# SIX_OUTPORT-V2.net
KiCad netlist of a schematic drawn in Altium Designer
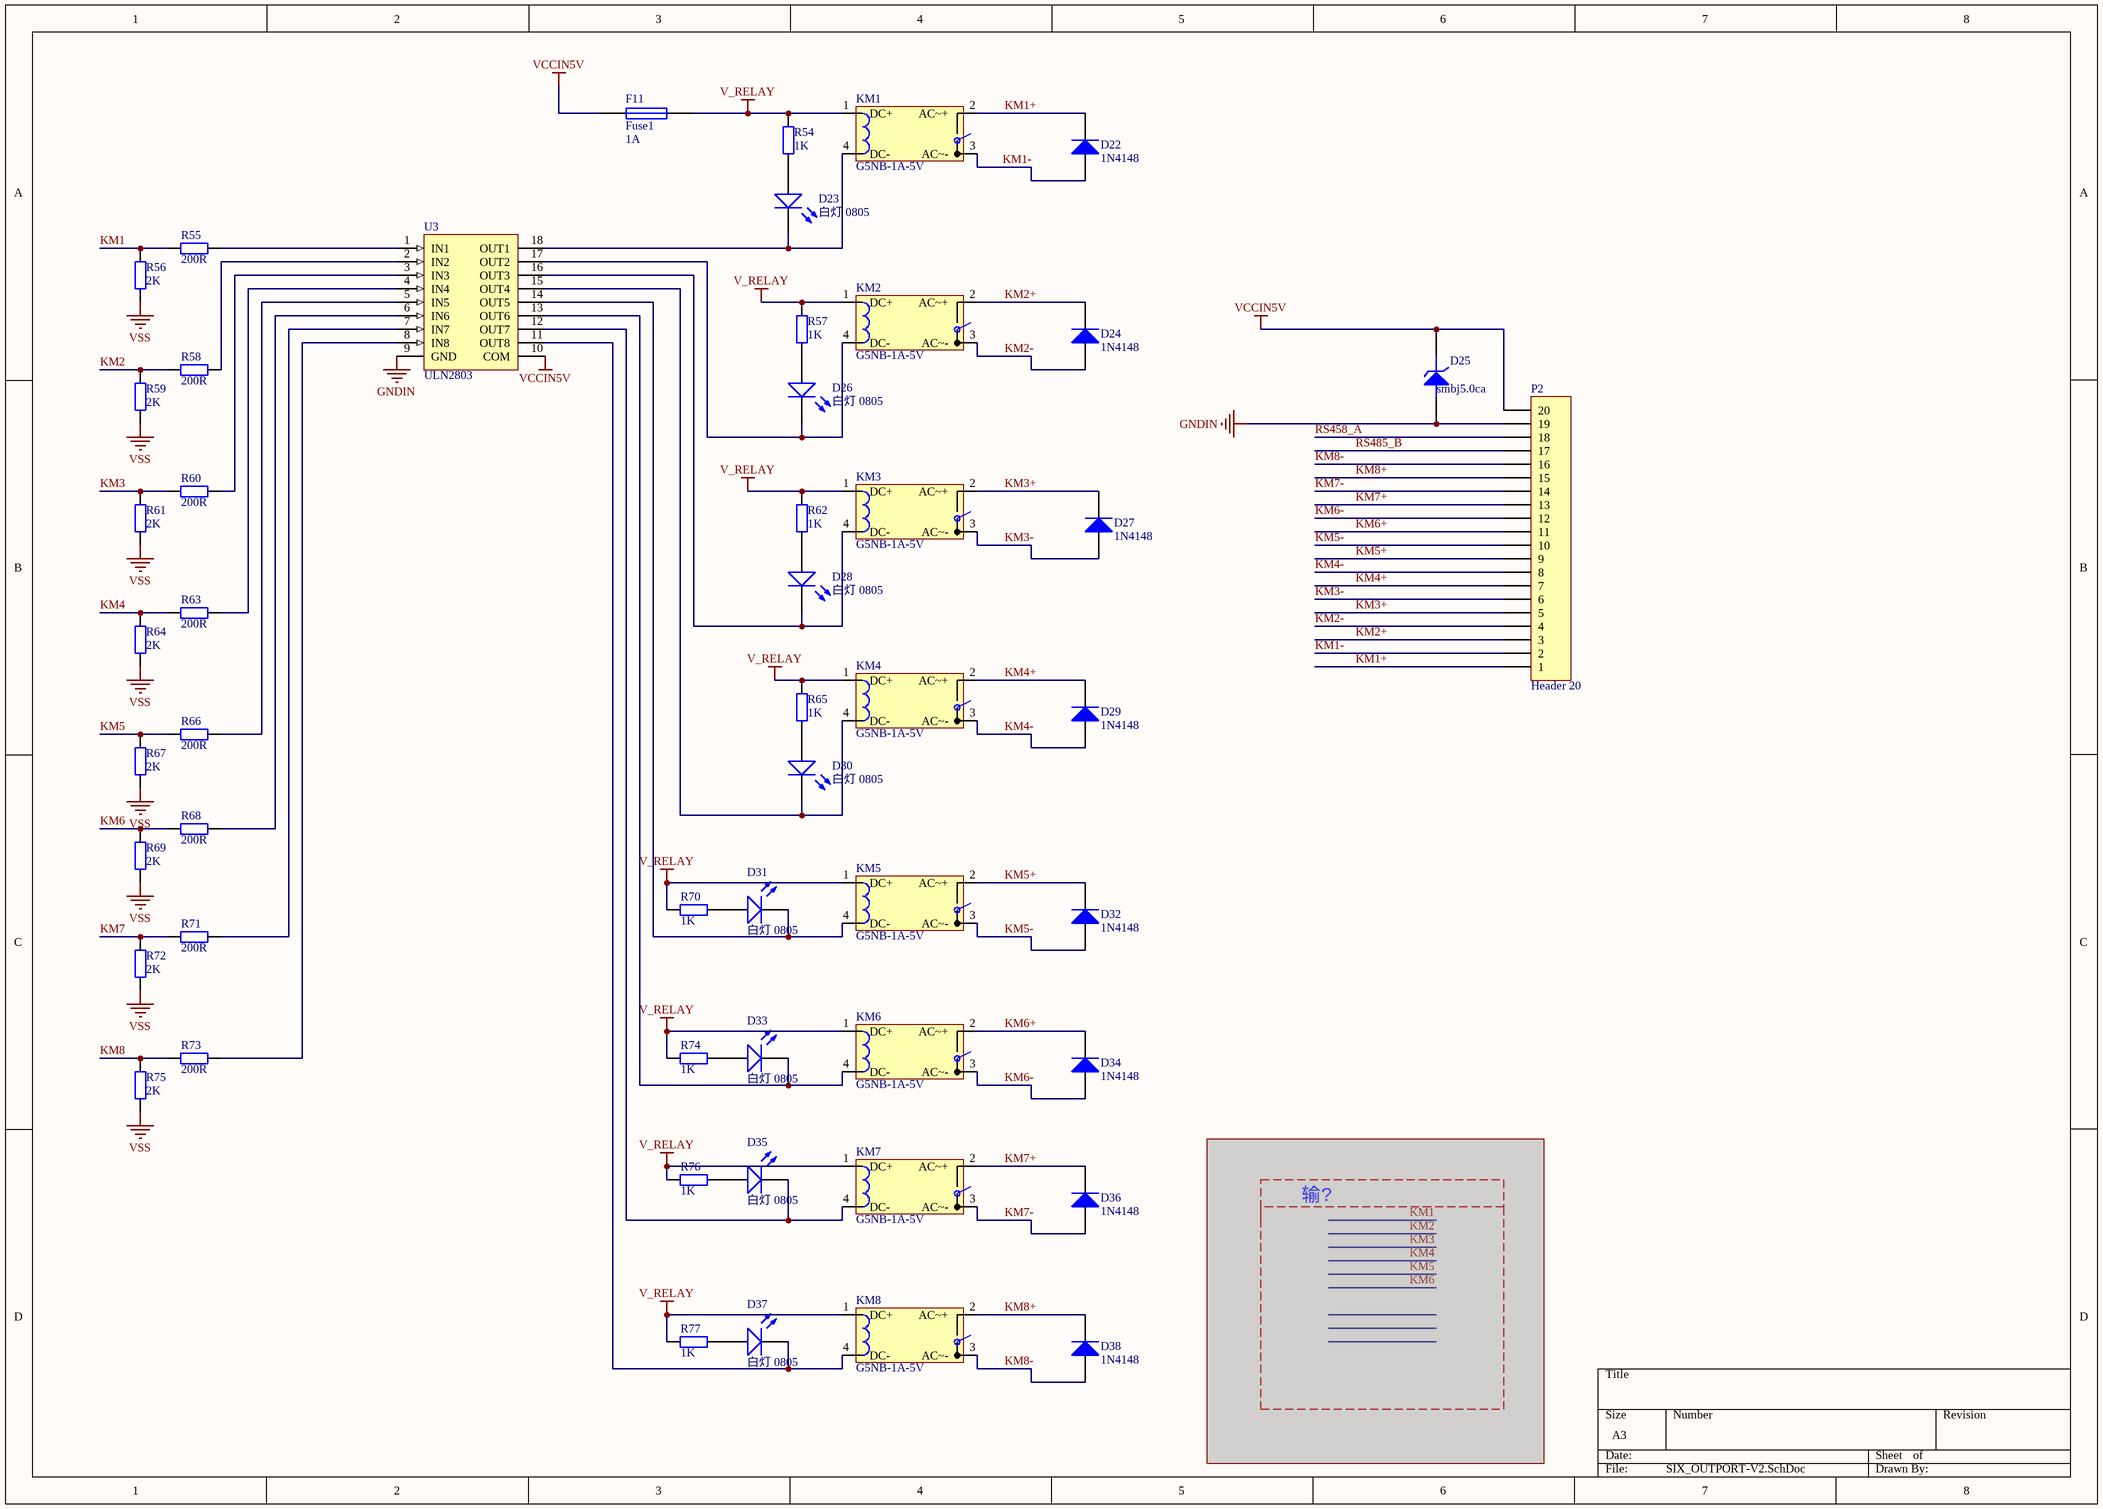
[diagram p0: SIX_OUTPORT-V2.SchDoc]

(export (version "E")
  (design (tool "Eeschema 10.0.6"))
  (components
    (comp (ref "D22")
      (value "1N4148")
      (footprint "LC-LL-34")
      (description "Default Diode")
      (fields (field (name "PUBLISHER") "Altium Limited"))
      (libsource (lib "Miscellaneous Devices") (part "Diode"))
    )
    (comp (ref "D23")
      (value "白灯 0805")
      (footprint "LC-0603_LED_S1")
      (description "发光二极管")
      (libsource (lib "Miscellaneous Devices LC") (part "0805 白灯"))
    )
    (comp (ref "D24")
      (value "1N4148")
      (footprint "LC-LL-34")
      (description "Default Diode")
      (fields (field (name "PUBLISHER") "Altium Limited"))
      (libsource (lib "Miscellaneous Devices") (part "Diode"))
    )
    (comp (ref "D25")
      (value "smbj5.0ca")
      (footprint "LC-SMB(DO-214AA)_S1")
      (description "Zener Diode")
      (libsource (lib "Miscellaneous Devices") (part "ZENER3"))
    )
    (comp (ref "D26")
      (value "白灯 0805")
      (footprint "LC-0603_LED_S1")
      (description "发光二极管")
      (libsource (lib "Miscellaneous Devices LC") (part "0805 白灯"))
    )
    (comp (ref "D27")
      (value "1N4148")
      (footprint "LC-LL-34")
      (description "Default Diode")
      (fields (field (name "PUBLISHER") "Altium Limited"))
      (libsource (lib "Miscellaneous Devices") (part "Diode"))
    )
    (comp (ref "D28")
      (value "白灯 0805")
      (footprint "LC-0603_LED_S1")
      (description "发光二极管")
      (libsource (lib "Miscellaneous Devices LC") (part "0805 白灯"))
    )
    (comp (ref "D29")
      (value "1N4148")
      (footprint "LC-LL-34")
      (description "Default Diode")
      (fields (field (name "PUBLISHER") "Altium Limited"))
      (libsource (lib "Miscellaneous Devices") (part "Diode"))
    )
    (comp (ref "D30")
      (value "白灯 0805")
      (footprint "LC-0603_LED_S1")
      (description "发光二极管")
      (libsource (lib "Miscellaneous Devices LC") (part "0805 白灯"))
    )
    (comp (ref "D31")
      (value "白灯 0805")
      (footprint "LC-0603_LED_S1")
      (description "发光二极管")
      (libsource (lib "Miscellaneous Devices LC") (part "0805 白灯"))
    )
    (comp (ref "D32")
      (value "1N4148")
      (footprint "LC-LL-34")
      (description "Default Diode")
      (fields (field (name "PUBLISHER") "Altium Limited"))
      (libsource (lib "Miscellaneous Devices") (part "Diode"))
    )
    (comp (ref "D33")
      (value "白灯 0805")
      (footprint "LC-0603_LED_S1")
      (description "发光二极管")
      (libsource (lib "Miscellaneous Devices LC") (part "0805 白灯"))
    )
    (comp (ref "D34")
      (value "1N4148")
      (footprint "LC-LL-34")
      (description "Default Diode")
      (fields (field (name "PUBLISHER") "Altium Limited"))
      (libsource (lib "Miscellaneous Devices") (part "Diode"))
    )
    (comp (ref "D35")
      (value "白灯 0805")
      (footprint "LC-0603_LED_S1")
      (description "发光二极管")
      (libsource (lib "Miscellaneous Devices LC") (part "0805 白灯"))
    )
    (comp (ref "D36")
      (value "1N4148")
      (footprint "LC-LL-34")
      (description "Default Diode")
      (fields (field (name "PUBLISHER") "Altium Limited"))
      (libsource (lib "Miscellaneous Devices") (part "Diode"))
    )
    (comp (ref "D37")
      (value "白灯 0805")
      (footprint "LC-0603_LED_S1")
      (description "发光二极管")
      (libsource (lib "Miscellaneous Devices LC") (part "0805 白灯"))
    )
    (comp (ref "D38")
      (value "1N4148")
      (footprint "LC-LL-34")
      (description "Default Diode")
      (fields (field (name "PUBLISHER") "Altium Limited"))
      (libsource (lib "Miscellaneous Devices") (part "Diode"))
    )
    (comp (ref "F11")
      (value "Fuse1")
      (footprint "LC-1206_R")
      (description "保险丝")
      (fields (field (name "ALTIUM_VALUE") "1A"))
      (libsource (lib "fszhang") (part "Fuse1"))
    )
    (comp (ref "KM1")
      (value "G5NB-1A-5V")
      (footprint "G5NB-1A-5V")
      (libsource (lib "fszhang") (part "G5NB-1A-5V"))
    )
    (comp (ref "KM2")
      (value "G5NB-1A-5V")
      (footprint "G5NB-1A-5V")
      (libsource (lib "fszhang") (part "G5NB-1A-5V"))
    )
    (comp (ref "KM3")
      (value "G5NB-1A-5V")
      (footprint "G5NB-1A-5V")
      (libsource (lib "fszhang") (part "G5NB-1A-5V"))
    )
    (comp (ref "KM4")
      (value "G5NB-1A-5V")
      (footprint "G5NB-1A-5V")
      (libsource (lib "fszhang") (part "G5NB-1A-5V"))
    )
    (comp (ref "KM5")
      (value "G5NB-1A-5V")
      (footprint "G5NB-1A-5V")
      (libsource (lib "fszhang") (part "G5NB-1A-5V"))
    )
    (comp (ref "KM6")
      (value "G5NB-1A-5V")
      (footprint "G5NB-1A-5V")
      (libsource (lib "fszhang") (part "G5NB-1A-5V"))
    )
    (comp (ref "KM7")
      (value "G5NB-1A-5V")
      (footprint "G5NB-1A-5V")
      (libsource (lib "fszhang") (part "G5NB-1A-5V"))
    )
    (comp (ref "KM8")
      (value "G5NB-1A-5V")
      (footprint "G5NB-1A-5V")
      (libsource (lib "fszhang") (part "G5NB-1A-5V"))
    )
    (comp (ref "P2")
      (value "Header 20")
      (footprint "HDR_5.0_20P")
      (description "Header, 20-Pin")
      (fields (field (name "PUBLISHER") "Altium Limited"))
      (libsource (lib "Miscellaneous Connectors") (part "Header 20"))
    )
    (comp (ref "R54")
      (value "1K")
      (footprint "LC-0603_R")
      (description "Resistor")
      (fields (field (name "PUBLISHER") "Altium Limited"))
      (libsource (lib "") (part "Res2_1"))
    )
    (comp (ref "R55")
      (value "200R")
      (footprint "LC-0603_R")
      (description "Resistor")
      (fields (field (name "PUBLISHER") "Altium Limited"))
      (libsource (lib "") (part "Res2_2"))
    )
    (comp (ref "R56")
      (value "2K")
      (footprint "LC-0603_R")
      (description "Resistor")
      (fields (field (name "PUBLISHER") "Altium Limited"))
      (libsource (lib "") (part "Res2_1"))
    )
    (comp (ref "R57")
      (value "1K")
      (footprint "LC-0603_R")
      (description "Resistor")
      (fields (field (name "PUBLISHER") "Altium Limited"))
      (libsource (lib "") (part "Res2_1"))
    )
    (comp (ref "R58")
      (value "200R")
      (footprint "LC-0603_R")
      (description "Resistor")
      (fields (field (name "PUBLISHER") "Altium Limited"))
      (libsource (lib "") (part "Res2_2"))
    )
    (comp (ref "R59")
      (value "2K")
      (footprint "LC-0603_R")
      (description "Resistor")
      (fields (field (name "PUBLISHER") "Altium Limited"))
      (libsource (lib "") (part "Res2_1"))
    )
    (comp (ref "R60")
      (value "200R")
      (footprint "LC-0603_R")
      (description "Resistor")
      (fields (field (name "PUBLISHER") "Altium Limited"))
      (libsource (lib "") (part "Res2_2"))
    )
    (comp (ref "R61")
      (value "2K")
      (footprint "LC-0603_R")
      (description "Resistor")
      (fields (field (name "PUBLISHER") "Altium Limited"))
      (libsource (lib "") (part "Res2_1"))
    )
    (comp (ref "R62")
      (value "1K")
      (footprint "LC-0603_R")
      (description "Resistor")
      (fields (field (name "PUBLISHER") "Altium Limited"))
      (libsource (lib "") (part "Res2_1"))
    )
    (comp (ref "R63")
      (value "200R")
      (footprint "LC-0603_R")
      (description "Resistor")
      (fields (field (name "PUBLISHER") "Altium Limited"))
      (libsource (lib "") (part "Res2_2"))
    )
    (comp (ref "R64")
      (value "2K")
      (footprint "LC-0603_R")
      (description "Resistor")
      (fields (field (name "PUBLISHER") "Altium Limited"))
      (libsource (lib "") (part "Res2_1"))
    )
    (comp (ref "R65")
      (value "1K")
      (footprint "LC-0603_R")
      (description "Resistor")
      (fields (field (name "PUBLISHER") "Altium Limited"))
      (libsource (lib "") (part "Res2_1"))
    )
    (comp (ref "R66")
      (value "200R")
      (footprint "LC-0603_R")
      (description "Resistor")
      (fields (field (name "PUBLISHER") "Altium Limited"))
      (libsource (lib "") (part "Res2_2"))
    )
    (comp (ref "R67")
      (value "2K")
      (footprint "LC-0603_R")
      (description "Resistor")
      (fields (field (name "PUBLISHER") "Altium Limited"))
      (libsource (lib "") (part "Res2_1"))
    )
    (comp (ref "R68")
      (value "200R")
      (footprint "LC-0603_R")
      (description "Resistor")
      (fields (field (name "PUBLISHER") "Altium Limited"))
      (libsource (lib "") (part "Res2_2"))
    )
    (comp (ref "R69")
      (value "2K")
      (footprint "LC-0603_R")
      (description "Resistor")
      (fields (field (name "PUBLISHER") "Altium Limited"))
      (libsource (lib "") (part "Res2_1"))
    )
    (comp (ref "R70")
      (value "1K")
      (footprint "LC-0603_R")
      (description "Resistor")
      (fields (field (name "PUBLISHER") "Altium Limited"))
      (libsource (lib "Miscellaneous Devices") (part "Res2"))
    )
    (comp (ref "R71")
      (value "200R")
      (footprint "LC-0603_R")
      (description "Resistor")
      (fields (field (name "PUBLISHER") "Altium Limited"))
      (libsource (lib "") (part "Res2_2"))
    )
    (comp (ref "R72")
      (value "2K")
      (footprint "LC-0603_R")
      (description "Resistor")
      (fields (field (name "PUBLISHER") "Altium Limited"))
      (libsource (lib "") (part "Res2_1"))
    )
    (comp (ref "R73")
      (value "200R")
      (footprint "LC-0603_R")
      (description "Resistor")
      (fields (field (name "PUBLISHER") "Altium Limited"))
      (libsource (lib "") (part "Res2_2"))
    )
    (comp (ref "R74")
      (value "1K")
      (footprint "LC-0603_R")
      (description "Resistor")
      (fields (field (name "PUBLISHER") "Altium Limited"))
      (libsource (lib "Miscellaneous Devices") (part "Res2"))
    )
    (comp (ref "R75")
      (value "2K")
      (footprint "LC-0603_R")
      (description "Resistor")
      (fields (field (name "PUBLISHER") "Altium Limited"))
      (libsource (lib "") (part "Res2_1"))
    )
    (comp (ref "R76")
      (value "1K")
      (footprint "LC-0603_R")
      (description "Resistor")
      (fields (field (name "PUBLISHER") "Altium Limited"))
      (libsource (lib "Miscellaneous Devices") (part "Res2"))
    )
    (comp (ref "R77")
      (value "1K")
      (footprint "LC-0603_R")
      (description "Resistor")
      (fields (field (name "PUBLISHER") "Altium Limited"))
      (libsource (lib "Miscellaneous Devices") (part "Res2"))
    )
    (comp (ref "U3")
      (value "ULN2803")
      (footprint "LC-SOIC-18_300mil")
      (libsource (lib "SCH_Footp1_Lian") (part "ULN2803"))
    )
  )
  (nets
    (net (code "1") (name "/KM1") (class "Default")
      (node (ref "R55") (pin "2") (pinfunction "2_2") (pintype "passive"))
      (node (ref "R56") (pin "1") (pinfunction "1_1") (pintype "passive"))
    )
    (net (code "2") (name "/KM1+") (class "Default")
      (node (ref "D22") (pin "2") (pinfunction "K_2") (pintype "passive"))
      (node (ref "KM1") (pin "2") (pinfunction "AC~+_2") (pintype "passive"))
      (node (ref "P2") (pin "1") (pinfunction "1_1") (pintype "passive"))
    )
    (net (code "3") (name "/KM1-") (class "Default")
      (node (ref "D22") (pin "1") (pinfunction "A_1") (pintype "passive"))
      (node (ref "KM1") (pin "3") (pinfunction "AC~-_3") (pintype "passive"))
      (node (ref "P2") (pin "2") (pinfunction "2_2") (pintype "passive"))
    )
    (net (code "4") (name "/KM2") (class "Default")
      (node (ref "R58") (pin "2") (pinfunction "2_2") (pintype "passive"))
      (node (ref "R59") (pin "1") (pinfunction "1_1") (pintype "passive"))
    )
    (net (code "5") (name "/KM2+") (class "Default")
      (node (ref "D24") (pin "2") (pinfunction "K_2") (pintype "passive"))
      (node (ref "KM2") (pin "2") (pinfunction "AC~+_2") (pintype "passive"))
      (node (ref "P2") (pin "3") (pinfunction "3_3") (pintype "passive"))
    )
    (net (code "6") (name "/KM2-") (class "Default")
      (node (ref "D24") (pin "1") (pinfunction "A_1") (pintype "passive"))
      (node (ref "KM2") (pin "3") (pinfunction "AC~-_3") (pintype "passive"))
      (node (ref "P2") (pin "4") (pinfunction "4_4") (pintype "passive"))
    )
    (net (code "7") (name "/KM3") (class "Default")
      (node (ref "R60") (pin "2") (pinfunction "2_2") (pintype "passive"))
      (node (ref "R61") (pin "1") (pinfunction "1_1") (pintype "passive"))
    )
    (net (code "8") (name "/KM3+") (class "Default")
      (node (ref "D27") (pin "2") (pinfunction "K_2") (pintype "passive"))
      (node (ref "KM3") (pin "2") (pinfunction "AC~+_2") (pintype "passive"))
      (node (ref "P2") (pin "5") (pinfunction "5_5") (pintype "passive"))
    )
    (net (code "9") (name "/KM3-") (class "Default")
      (node (ref "D27") (pin "1") (pinfunction "A_1") (pintype "passive"))
      (node (ref "KM3") (pin "3") (pinfunction "AC~-_3") (pintype "passive"))
      (node (ref "P2") (pin "6") (pinfunction "6_6") (pintype "passive"))
    )
    (net (code "10") (name "/KM4") (class "Default")
      (node (ref "R63") (pin "2") (pinfunction "2_2") (pintype "passive"))
      (node (ref "R64") (pin "1") (pinfunction "1_1") (pintype "passive"))
    )
    (net (code "11") (name "/KM4+") (class "Default")
      (node (ref "D29") (pin "2") (pinfunction "K_2") (pintype "passive"))
      (node (ref "KM4") (pin "2") (pinfunction "AC~+_2") (pintype "passive"))
      (node (ref "P2") (pin "7") (pinfunction "7_7") (pintype "passive"))
    )
    (net (code "12") (name "/KM4-") (class "Default")
      (node (ref "D29") (pin "1") (pinfunction "A_1") (pintype "passive"))
      (node (ref "KM4") (pin "3") (pinfunction "AC~-_3") (pintype "passive"))
      (node (ref "P2") (pin "8") (pinfunction "8_8") (pintype "passive"))
    )
    (net (code "13") (name "/KM5") (class "Default")
      (node (ref "R66") (pin "2") (pinfunction "2_2") (pintype "passive"))
      (node (ref "R67") (pin "1") (pinfunction "1_1") (pintype "passive"))
    )
    (net (code "14") (name "/KM5+") (class "Default")
      (node (ref "D32") (pin "2") (pinfunction "K_2") (pintype "passive"))
      (node (ref "KM5") (pin "2") (pinfunction "AC~+_2") (pintype "passive"))
      (node (ref "P2") (pin "9") (pinfunction "9_9") (pintype "passive"))
    )
    (net (code "15") (name "/KM5-") (class "Default")
      (node (ref "D32") (pin "1") (pinfunction "A_1") (pintype "passive"))
      (node (ref "KM5") (pin "3") (pinfunction "AC~-_3") (pintype "passive"))
      (node (ref "P2") (pin "10") (pinfunction "10_10") (pintype "passive"))
    )
    (net (code "16") (name "/KM6") (class "Default")
      (node (ref "R68") (pin "2") (pinfunction "2_2") (pintype "passive"))
      (node (ref "R69") (pin "1") (pinfunction "1_1") (pintype "passive"))
    )
    (net (code "17") (name "/KM6+") (class "Default")
      (node (ref "D34") (pin "2") (pinfunction "K_2") (pintype "passive"))
      (node (ref "KM6") (pin "2") (pinfunction "AC~+_2") (pintype "passive"))
      (node (ref "P2") (pin "11") (pinfunction "11_11") (pintype "passive"))
    )
    (net (code "18") (name "/KM6-") (class "Default")
      (node (ref "D34") (pin "1") (pinfunction "A_1") (pintype "passive"))
      (node (ref "KM6") (pin "3") (pinfunction "AC~-_3") (pintype "passive"))
      (node (ref "P2") (pin "12") (pinfunction "12_12") (pintype "passive"))
    )
    (net (code "19") (name "/KM7") (class "Default")
      (node (ref "R71") (pin "2") (pinfunction "2_2") (pintype "passive"))
      (node (ref "R72") (pin "1") (pinfunction "1_1") (pintype "passive"))
    )
    (net (code "20") (name "/KM7+") (class "Default")
      (node (ref "D36") (pin "2") (pinfunction "K_2") (pintype "passive"))
      (node (ref "KM7") (pin "2") (pinfunction "AC~+_2") (pintype "passive"))
      (node (ref "P2") (pin "13") (pinfunction "13_13") (pintype "passive"))
    )
    (net (code "21") (name "/KM7-") (class "Default")
      (node (ref "D36") (pin "1") (pinfunction "A_1") (pintype "passive"))
      (node (ref "KM7") (pin "3") (pinfunction "AC~-_3") (pintype "passive"))
      (node (ref "P2") (pin "14") (pinfunction "14_14") (pintype "passive"))
    )
    (net (code "22") (name "/KM8") (class "Default")
      (node (ref "R73") (pin "2") (pinfunction "2_2") (pintype "passive"))
      (node (ref "R75") (pin "1") (pinfunction "1_1") (pintype "passive"))
    )
    (net (code "23") (name "/KM8+") (class "Default")
      (node (ref "D38") (pin "2") (pinfunction "K_2") (pintype "passive"))
      (node (ref "KM8") (pin "2") (pinfunction "AC~+_2") (pintype "passive"))
      (node (ref "P2") (pin "15") (pinfunction "15_15") (pintype "passive"))
    )
    (net (code "24") (name "/KM8-") (class "Default")
      (node (ref "D38") (pin "1") (pinfunction "A_1") (pintype "passive"))
      (node (ref "KM8") (pin "3") (pinfunction "AC~-_3") (pintype "passive"))
      (node (ref "P2") (pin "16") (pinfunction "16_16") (pintype "passive"))
    )
    (net (code "25") (name "/RS458_A") (class "Default")
      (node (ref "P2") (pin "18") (pinfunction "18_18") (pintype "passive"))
    )
    (net (code "26") (name "/RS485_B") (class "Default")
      (node (ref "P2") (pin "17") (pinfunction "17_17") (pintype "passive"))
    )
    (net (code "27") (name "GNDIN") (class "Default")
      (node (ref "D25") (pin "1") (pinfunction "A_1") (pintype "passive"))
      (node (ref "P2") (pin "19") (pinfunction "19_19") (pintype "passive"))
      (node (ref "U3") (pin "9") (pinfunction "GND_9") (pintype "power_in"))
    )
    (net (code "28") (name "Net-(D23-PadA)") (class "Default")
      (node (ref "D23") (pin "A") (pinfunction "A_A") (pintype "passive"))
      (node (ref "R54") (pin "2") (pinfunction "2_2") (pintype "passive"))
    )
    (net (code "29") (name "Net-(D26-PadA)") (class "Default")
      (node (ref "D26") (pin "A") (pinfunction "A_A") (pintype "passive"))
      (node (ref "R57") (pin "2") (pinfunction "2_2") (pintype "passive"))
    )
    (net (code "30") (name "Net-(D28-PadA)") (class "Default")
      (node (ref "D28") (pin "A") (pinfunction "A_A") (pintype "passive"))
      (node (ref "R62") (pin "2") (pinfunction "2_2") (pintype "passive"))
    )
    (net (code "31") (name "Net-(D30-PadA)") (class "Default")
      (node (ref "D30") (pin "A") (pinfunction "A_A") (pintype "passive"))
      (node (ref "R65") (pin "2") (pinfunction "2_2") (pintype "passive"))
    )
    (net (code "32") (name "Net-(D31-PadA)") (class "Default")
      (node (ref "D31") (pin "A") (pinfunction "A_A") (pintype "passive"))
      (node (ref "R70") (pin "2") (pinfunction "2_2") (pintype "passive"))
    )
    (net (code "33") (name "Net-(D33-PadA)") (class "Default")
      (node (ref "D33") (pin "A") (pinfunction "A_A") (pintype "passive"))
      (node (ref "R74") (pin "2") (pinfunction "2_2") (pintype "passive"))
    )
    (net (code "34") (name "Net-(D35-PadA)") (class "Default")
      (node (ref "D35") (pin "A") (pinfunction "A_A") (pintype "passive"))
      (node (ref "R76") (pin "2") (pinfunction "2_2") (pintype "passive"))
    )
    (net (code "35") (name "Net-(D37-PadA)") (class "Default")
      (node (ref "D37") (pin "A") (pinfunction "A_A") (pintype "passive"))
      (node (ref "R77") (pin "2") (pinfunction "2_2") (pintype "passive"))
    )
    (net (code "36") (name "Net-(KM1-DC-)") (class "Default")
      (node (ref "D23") (pin "K") (pinfunction "K_K") (pintype "passive"))
      (node (ref "KM1") (pin "4") (pinfunction "DC-_4") (pintype "passive"))
      (node (ref "U3") (pin "18") (pinfunction "OUT1_18") (pintype "open_collector"))
    )
    (net (code "37") (name "Net-(KM2-DC-)") (class "Default")
      (node (ref "D26") (pin "K") (pinfunction "K_K") (pintype "passive"))
      (node (ref "KM2") (pin "4") (pinfunction "DC-_4") (pintype "passive"))
      (node (ref "U3") (pin "17") (pinfunction "OUT2_17") (pintype "open_collector"))
    )
    (net (code "38") (name "Net-(KM3-DC-)") (class "Default")
      (node (ref "D28") (pin "K") (pinfunction "K_K") (pintype "passive"))
      (node (ref "KM3") (pin "4") (pinfunction "DC-_4") (pintype "passive"))
      (node (ref "U3") (pin "16") (pinfunction "OUT3_16") (pintype "open_collector"))
    )
    (net (code "39") (name "Net-(KM4-DC-)") (class "Default")
      (node (ref "D30") (pin "K") (pinfunction "K_K") (pintype "passive"))
      (node (ref "KM4") (pin "4") (pinfunction "DC-_4") (pintype "passive"))
      (node (ref "U3") (pin "15") (pinfunction "OUT4_15") (pintype "open_collector"))
    )
    (net (code "40") (name "Net-(KM5-DC-)") (class "Default")
      (node (ref "D31") (pin "K") (pinfunction "K_K") (pintype "passive"))
      (node (ref "KM5") (pin "4") (pinfunction "DC-_4") (pintype "passive"))
      (node (ref "U3") (pin "14") (pinfunction "OUT5_14") (pintype "open_collector"))
    )
    (net (code "41") (name "Net-(KM6-DC-)") (class "Default")
      (node (ref "D33") (pin "K") (pinfunction "K_K") (pintype "passive"))
      (node (ref "KM6") (pin "4") (pinfunction "DC-_4") (pintype "passive"))
      (node (ref "U3") (pin "13") (pinfunction "OUT6_13") (pintype "open_collector"))
    )
    (net (code "42") (name "Net-(KM7-DC-)") (class "Default")
      (node (ref "D35") (pin "K") (pinfunction "K_K") (pintype "passive"))
      (node (ref "KM7") (pin "4") (pinfunction "DC-_4") (pintype "passive"))
      (node (ref "U3") (pin "12") (pinfunction "OUT7_12") (pintype "open_collector"))
    )
    (net (code "43") (name "Net-(KM8-DC-)") (class "Default")
      (node (ref "D37") (pin "K") (pinfunction "K_K") (pintype "passive"))
      (node (ref "KM8") (pin "4") (pinfunction "DC-_4") (pintype "passive"))
      (node (ref "U3") (pin "11") (pinfunction "OUT8_11") (pintype "passive"))
    )
    (net (code "44") (name "Net-(U3-IN1)") (class "Default")
      (node (ref "R55") (pin "1") (pinfunction "1_1") (pintype "passive"))
      (node (ref "U3") (pin "1") (pinfunction "IN1_1") (pintype "input"))
    )
    (net (code "45") (name "Net-(U3-IN2)") (class "Default")
      (node (ref "R58") (pin "1") (pinfunction "1_1") (pintype "passive"))
      (node (ref "U3") (pin "2") (pinfunction "IN2_2") (pintype "input"))
    )
    (net (code "46") (name "Net-(U3-IN3)") (class "Default")
      (node (ref "R60") (pin "1") (pinfunction "1_1") (pintype "passive"))
      (node (ref "U3") (pin "3") (pinfunction "IN3_3") (pintype "input"))
    )
    (net (code "47") (name "Net-(U3-IN4)") (class "Default")
      (node (ref "R63") (pin "1") (pinfunction "1_1") (pintype "passive"))
      (node (ref "U3") (pin "4") (pinfunction "IN4_4") (pintype "input"))
    )
    (net (code "48") (name "Net-(U3-IN5)") (class "Default")
      (node (ref "R66") (pin "1") (pinfunction "1_1") (pintype "passive"))
      (node (ref "U3") (pin "5") (pinfunction "IN5_5") (pintype "input"))
    )
    (net (code "49") (name "Net-(U3-IN6)") (class "Default")
      (node (ref "R68") (pin "1") (pinfunction "1_1") (pintype "passive"))
      (node (ref "U3") (pin "6") (pinfunction "IN6_6") (pintype "input"))
    )
    (net (code "50") (name "Net-(U3-IN7)") (class "Default")
      (node (ref "R71") (pin "1") (pinfunction "1_1") (pintype "passive"))
      (node (ref "U3") (pin "7") (pinfunction "IN7_7") (pintype "input"))
    )
    (net (code "51") (name "Net-(U3-IN8)") (class "Default")
      (node (ref "R73") (pin "1") (pinfunction "1_1") (pintype "passive"))
      (node (ref "U3") (pin "8") (pinfunction "IN8_8") (pintype "input"))
    )
    (net (code "52") (name "VCCIN5V") (class "Default")
      (node (ref "D25") (pin "2") (pinfunction "K_2") (pintype "passive"))
      (node (ref "F11") (pin "1") (pinfunction "1_1") (pintype "passive"))
      (node (ref "P2") (pin "20") (pinfunction "20_20") (pintype "passive"))
      (node (ref "U3") (pin "10") (pinfunction "COM_10") (pintype "passive"))
    )
    (net (code "53") (name "VSS") (class "Default")
      (node (ref "R56") (pin "2") (pinfunction "2_2") (pintype "passive"))
      (node (ref "R59") (pin "2") (pinfunction "2_2") (pintype "passive"))
      (node (ref "R61") (pin "2") (pinfunction "2_2") (pintype "passive"))
      (node (ref "R64") (pin "2") (pinfunction "2_2") (pintype "passive"))
      (node (ref "R67") (pin "2") (pinfunction "2_2") (pintype "passive"))
      (node (ref "R69") (pin "2") (pinfunction "2_2") (pintype "passive"))
      (node (ref "R72") (pin "2") (pinfunction "2_2") (pintype "passive"))
      (node (ref "R75") (pin "2") (pinfunction "2_2") (pintype "passive"))
    )
    (net (code "54") (name "V_RELAY") (class "Default")
      (node (ref "F11") (pin "2") (pinfunction "2_2") (pintype "passive"))
      (node (ref "KM1") (pin "1") (pinfunction "DC+_1") (pintype "passive"))
      (node (ref "KM2") (pin "1") (pinfunction "DC+_1") (pintype "passive"))
      (node (ref "KM3") (pin "1") (pinfunction "DC+_1") (pintype "passive"))
      (node (ref "KM4") (pin "1") (pinfunction "DC+_1") (pintype "passive"))
      (node (ref "KM5") (pin "1") (pinfunction "DC+_1") (pintype "passive"))
      (node (ref "KM6") (pin "1") (pinfunction "DC+_1") (pintype "passive"))
      (node (ref "KM7") (pin "1") (pinfunction "DC+_1") (pintype "passive"))
      (node (ref "KM8") (pin "1") (pinfunction "DC+_1") (pintype "passive"))
      (node (ref "R54") (pin "1") (pinfunction "1_1") (pintype "passive"))
      (node (ref "R57") (pin "1") (pinfunction "1_1") (pintype "passive"))
      (node (ref "R62") (pin "1") (pinfunction "1_1") (pintype "passive"))
      (node (ref "R65") (pin "1") (pinfunction "1_1") (pintype "passive"))
      (node (ref "R70") (pin "1") (pinfunction "1_1") (pintype "passive"))
      (node (ref "R74") (pin "1") (pinfunction "1_1") (pintype "passive"))
      (node (ref "R76") (pin "1") (pinfunction "1_1") (pintype "passive"))
      (node (ref "R77") (pin "1") (pinfunction "1_1") (pintype "passive"))
    )
  )
)
